# V1_4.net
KiCad netlist of a schematic drawn in Altium Designer
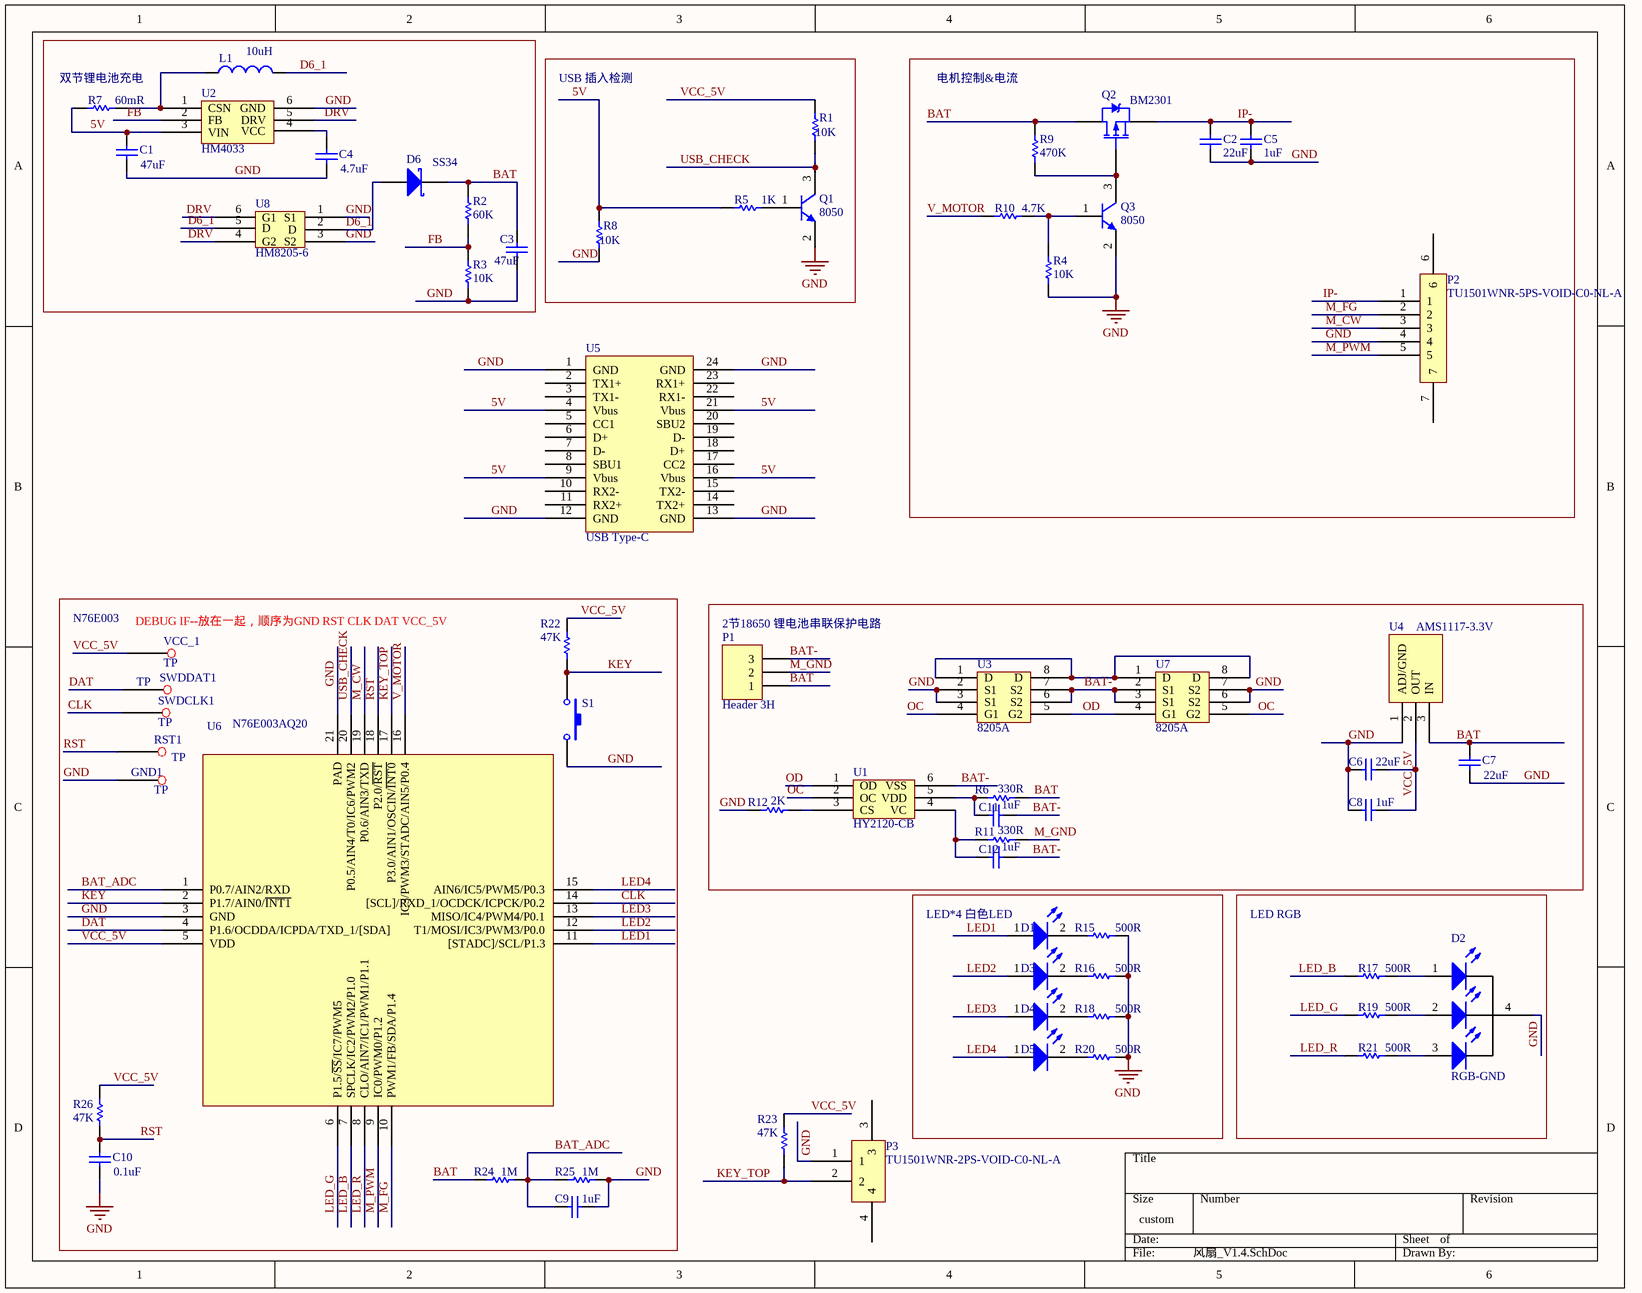
[diagram p0: 风扇_V1.4.SchDoc]

(export (version "E")
  (design (tool "Eeschema 10.0.6"))
  (components
    (comp (ref "C1")
      (value "47uF")
      (footprint "C-0603")
      (description "Capacitor")
      (fields (field (name "PUBLISHER") "Altium Limited"))
      (libsource (lib "Miscellaneous Devices") (part "Cap"))
    )
    (comp (ref "C2")
      (value "22uF")
      (footprint "C-0603")
      (description "Capacitor")
      (fields (field (name "PUBLISHER") "Altium Limited"))
      (libsource (lib "Miscellaneous Devices") (part "Cap"))
    )
    (comp (ref "C3")
      (value "47uF")
      (footprint "C-0603")
      (description "Capacitor")
      (fields (field (name "PUBLISHER") "Altium Limited"))
      (libsource (lib "Miscellaneous Devices") (part "Cap"))
    )
    (comp (ref "C4")
      (value "4.7uF")
      (footprint "C-0402")
      (description "Capacitor")
      (fields (field (name "PUBLISHER") "Altium Limited"))
      (libsource (lib "Miscellaneous Devices") (part "Cap"))
    )
    (comp (ref "C5")
      (value "1uF")
      (footprint "C-0402")
      (description "Capacitor")
      (fields (field (name "PUBLISHER") "Altium Limited"))
      (libsource (lib "Miscellaneous Devices") (part "Cap"))
    )
    (comp (ref "C6")
      (value "22uF")
      (footprint "C-0603")
      (description "Capacitor")
      (fields (field (name "PUBLISHER") "Altium Limited"))
      (libsource (lib "Miscellaneous Devices") (part "Cap"))
    )
    (comp (ref "C7")
      (value "22uF")
      (footprint "C-0603")
      (description "Capacitor")
      (fields (field (name "PUBLISHER") "Altium Limited"))
      (libsource (lib "Miscellaneous Devices") (part "Cap"))
    )
    (comp (ref "C8")
      (value "1uF")
      (footprint "C-0402")
      (description "Capacitor")
      (fields (field (name "PUBLISHER") "Altium Limited"))
      (libsource (lib "Miscellaneous Devices") (part "Cap"))
    )
    (comp (ref "C9")
      (value "1uF")
      (footprint "C-0402")
      (description "Capacitor")
      (fields (field (name "PUBLISHER") "Altium Limited"))
      (libsource (lib "Miscellaneous Devices") (part "Cap"))
    )
    (comp (ref "C10")
      (value "0.1uF")
      (footprint "C-0402")
      (description "Capacitor")
      (fields (field (name "PUBLISHER") "Altium Limited"))
      (libsource (lib "Miscellaneous Devices") (part "Cap"))
    )
    (comp (ref "C11")
      (value "1uF")
      (footprint "C-0402")
      (description "Capacitor")
      (fields (field (name "PUBLISHER") "Altium Limited"))
      (libsource (lib "Miscellaneous Devices") (part "Cap"))
    )
    (comp (ref "C12")
      (value "1uF")
      (footprint "C-0402")
      (description "Capacitor")
      (fields (field (name "PUBLISHER") "Altium Limited"))
      (libsource (lib "Miscellaneous Devices") (part "Cap"))
    )
    (comp (ref "D1")
      (value "LED0")
      (footprint "LED-0603")
      (description "Typical INFRARED GaAs LED")
      (fields (field (name "PUBLISHER") "Altium Limited"))
      (libsource (lib "Miscellaneous Devices") (part "LED0"))
    )
    (comp (ref "D2")
      (value "RGB-GND")
      (footprint "0603*2-LED")
      (libsource (lib "Others_IC_SCH_LIB") (part "RGB-GND"))
    )
    (comp (ref "D3")
      (value "LED0")
      (footprint "LED-0603")
      (description "Typical INFRARED GaAs LED")
      (fields (field (name "PUBLISHER") "Altium Limited"))
      (libsource (lib "Miscellaneous Devices") (part "LED0"))
    )
    (comp (ref "D4")
      (value "LED0")
      (footprint "LED-0603")
      (description "Typical INFRARED GaAs LED")
      (fields (field (name "PUBLISHER") "Altium Limited"))
      (libsource (lib "Miscellaneous Devices") (part "LED0"))
    )
    (comp (ref "D5")
      (value "LED0")
      (footprint "LED-0603")
      (description "Typical INFRARED GaAs LED")
      (fields (field (name "PUBLISHER") "Altium Limited"))
      (libsource (lib "Miscellaneous Devices") (part "LED0"))
    )
    (comp (ref "D6")
      (value "SS34")
      (footprint "HM4033 V1.0:DSMD")
      (description "Schottky Rectifier")
      (fields (field (name "PUBLISHER") "Altium Limited"))
      (libsource (lib "Miscellaneous Devices") (part "Diode 10TQ035"))
    )
    (comp (ref "GND1") (value "TP") (footprint "TP-1.5") (libsource (lib "Others_IC_SCH_LIB") (part "TP")))
    (comp (ref "L1")
      (value "10uH")
      (footprint "L-SMD")
      (description "Inductor")
      (fields (field (name "PUBLISHER") "Altium Limited"))
      (libsource (lib "Miscellaneous Devices") (part "Inductor"))
    )
    (comp (ref "P1")
      (value "Header 3H")
      (footprint "3P-SMT-3*3")
      (description "Header, 3-Pin, Right Angle")
      (fields (field (name "PUBLISHER") "Altium Limited"))
      (libsource (lib "Miscellaneous Connectors") (part "Header 3H"))
    )
    (comp (ref "P2")
      (value "TU1501WNR-5PS-VOID-C0-NL-A")
      (footprint "TU1501WNR-5PS-VOID-*-NL-A")
      (libsource (lib "Others_IC_SCH_LIB") (part "TU1501WNR-5PS-VOID-C0-NL-A"))
    )
    (comp (ref "P3")
      (value "TU1501WNR-2PS-VOID-C0-NL-A")
      (footprint "TU1501WNR-2PS-VOID-*-NL-A")
      (libsource (lib "Others_IC_SCH_LIB") (part "TU1501WNR-2PS-VOID-C0-NL-A"))
    )
    (comp (ref "Q1")
      (value "8050")
      (footprint "SOT-23")
      (description "NPN Bipolar Transistor")
      (fields (field (name "PUBLISHER") "Altium Limited"))
      (libsource (lib "Miscellaneous Devices") (part "NPN"))
    )
    (comp (ref "Q2")
      (value "BM2301")
      (footprint "SOT-23")
      (description "P-Channel Power MOSFET")
      (fields (field (name "PUBLISHER") "Altium Limited"))
      (libsource (lib "Miscellaneous Devices") (part "PMOS-2"))
    )
    (comp (ref "Q3")
      (value "8050")
      (footprint "SOT-23")
      (description "NPN Bipolar Transistor")
      (fields (field (name "PUBLISHER") "Altium Limited"))
      (libsource (lib "Miscellaneous Devices") (part "NPN"))
    )
    (comp (ref "R1")
      (value "10K")
      (footprint "R-0402")
      (description "Resistor")
      (fields (field (name "PUBLISHER") "Altium Limited"))
      (libsource (lib "Miscellaneous Devices") (part "Res1"))
    )
    (comp (ref "R2")
      (value "60K")
      (footprint "R-0402")
      (description "Resistor")
      (fields (field (name "PUBLISHER") "Altium Limited"))
      (libsource (lib "Miscellaneous Devices") (part "Res1"))
    )
    (comp (ref "R3")
      (value "10K")
      (footprint "R-0402")
      (description "Resistor")
      (fields (field (name "PUBLISHER") "Altium Limited"))
      (libsource (lib "Miscellaneous Devices") (part "Res1"))
    )
    (comp (ref "R4")
      (value "10K")
      (footprint "R-0402")
      (description "Resistor")
      (fields (field (name "PUBLISHER") "Altium Limited"))
      (libsource (lib "Miscellaneous Devices") (part "Res1"))
    )
    (comp (ref "R5")
      (value "1K")
      (footprint "R-0402")
      (description "Resistor")
      (fields (field (name "PUBLISHER") "Altium Limited"))
      (libsource (lib "Miscellaneous Devices") (part "Res1"))
    )
    (comp (ref "R6")
      (value "330R")
      (footprint "R-0402")
      (description "Resistor")
      (fields (field (name "PUBLISHER") "Altium Limited"))
      (libsource (lib "Miscellaneous Devices") (part "Res1"))
    )
    (comp (ref "R7")
      (value "60mR")
      (footprint "R-0402")
      (description "Resistor")
      (fields (field (name "PUBLISHER") "Altium Limited"))
      (libsource (lib "Miscellaneous Devices") (part "Res1"))
    )
    (comp (ref "R8")
      (value "10K")
      (footprint "R-0402")
      (description "Resistor")
      (fields (field (name "PUBLISHER") "Altium Limited"))
      (libsource (lib "Miscellaneous Devices") (part "Res1"))
    )
    (comp (ref "R9")
      (value "470K")
      (footprint "R-0402")
      (description "Resistor")
      (fields (field (name "PUBLISHER") "Altium Limited"))
      (libsource (lib "Miscellaneous Devices") (part "Res1"))
    )
    (comp (ref "R10")
      (value "4.7K")
      (footprint "R-0402")
      (description "Resistor")
      (fields (field (name "PUBLISHER") "Altium Limited"))
      (libsource (lib "Miscellaneous Devices") (part "Res1"))
    )
    (comp (ref "R11")
      (value "330R")
      (footprint "R-0402")
      (description "Resistor")
      (fields (field (name "PUBLISHER") "Altium Limited"))
      (libsource (lib "Miscellaneous Devices") (part "Res1"))
    )
    (comp (ref "R12")
      (value "2K")
      (footprint "R-0402")
      (description "Resistor")
      (fields (field (name "PUBLISHER") "Altium Limited"))
      (libsource (lib "Miscellaneous Devices") (part "Res1"))
    )
    (comp (ref "R15")
      (value "500R")
      (footprint "R-0402")
      (description "Resistor")
      (fields (field (name "PUBLISHER") "Altium Limited"))
      (libsource (lib "Miscellaneous Devices") (part "Res1"))
    )
    (comp (ref "R16")
      (value "500R")
      (footprint "R-0402")
      (description "Resistor")
      (fields (field (name "PUBLISHER") "Altium Limited"))
      (libsource (lib "Miscellaneous Devices") (part "Res1"))
    )
    (comp (ref "R17")
      (value "500R")
      (footprint "R-0402")
      (description "Resistor")
      (fields (field (name "PUBLISHER") "Altium Limited"))
      (libsource (lib "Miscellaneous Devices") (part "Res1"))
    )
    (comp (ref "R18")
      (value "500R")
      (footprint "R-0402")
      (description "Resistor")
      (fields (field (name "PUBLISHER") "Altium Limited"))
      (libsource (lib "Miscellaneous Devices") (part "Res1"))
    )
    (comp (ref "R19")
      (value "500R")
      (footprint "R-0402")
      (description "Resistor")
      (fields (field (name "PUBLISHER") "Altium Limited"))
      (libsource (lib "Miscellaneous Devices") (part "Res1"))
    )
    (comp (ref "R20")
      (value "500R")
      (footprint "R-0402")
      (description "Resistor")
      (fields (field (name "PUBLISHER") "Altium Limited"))
      (libsource (lib "Miscellaneous Devices") (part "Res1"))
    )
    (comp (ref "R21")
      (value "500R")
      (footprint "R-0402")
      (description "Resistor")
      (fields (field (name "PUBLISHER") "Altium Limited"))
      (libsource (lib "Miscellaneous Devices") (part "Res1"))
    )
    (comp (ref "R22")
      (value "47K")
      (footprint "R-0402")
      (description "Resistor")
      (fields (field (name "PUBLISHER") "Altium Limited"))
      (libsource (lib "Miscellaneous Devices") (part "Res1"))
    )
    (comp (ref "R23")
      (value "47K")
      (footprint "R-0402")
      (description "Resistor")
      (fields (field (name "PUBLISHER") "Altium Limited"))
      (libsource (lib "Miscellaneous Devices") (part "Res1"))
    )
    (comp (ref "R24")
      (value "1M")
      (footprint "R-0402")
      (description "Resistor")
      (fields (field (name "PUBLISHER") "Altium Limited"))
      (libsource (lib "Miscellaneous Devices") (part "Res1"))
    )
    (comp (ref "R25")
      (value "1M")
      (footprint "R-0402")
      (description "Resistor")
      (fields (field (name "PUBLISHER") "Altium Limited"))
      (libsource (lib "Miscellaneous Devices") (part "Res1"))
    )
    (comp (ref "R26")
      (value "47K")
      (footprint "R-0402")
      (description "Resistor")
      (fields (field (name "PUBLISHER") "Altium Limited"))
      (libsource (lib "Miscellaneous Devices") (part "Res1"))
    )
    (comp (ref "RST1") (value "TP") (footprint "TP-1.5") (libsource (lib "Others_IC_SCH_LIB") (part "TP")))
    (comp (ref "S1")
      (value "SW-PB")
      (footprint "SWITCH-4P-SMT")
      (description "Switch")
      (fields (field (name "PUBLISHER") "Altium Limited"))
      (libsource (lib "Miscellaneous Devices") (part "SW-PB"))
    )
    (comp (ref "SWDCLK1") (value "TP") (footprint "TP-1.5") (libsource (lib "Others_IC_SCH_LIB") (part "TP")))
    (comp (ref "SWDDAT1") (value "TP") (footprint "TP-1.5") (libsource (lib "Others_IC_SCH_LIB") (part "TP")))
    (comp (ref "U1")
      (value "HY2120-CB")
      (footprint "SOT-23-6L")
      (libsource (lib "Others_IC_SCH_LIB") (part "HY2120"))
    )
    (comp (ref "U2")
      (value "HM4033")
      (footprint "SOT-23-6L")
      (libsource (lib "Others_IC_SCH_LIB") (part "HM4033"))
    )
    (comp (ref "U3")
      (value "8205A")
      (footprint "TSSOP8")
      (libsource (lib "Others_IC_SCH_LIB") (part "8205A"))
    )
    (comp (ref "U4")
      (value "AMS1117-3.3V")
      (footprint "SOT-223")
      (libsource (lib "Others_IC_SCH_LIB") (part "AMS1117"))
    )
    (comp (ref "U5")
      (value "USB Type-C")
      (footprint "USB-type C")
      (libsource (lib "Others_IC_SCH_LIB") (part "USB Type-C"))
    )
    (comp (ref "U6")
      (value "N76E003AQ20")
      (footprint "QFN-20 0.4mm")
      (libsource (lib "Others_IC_SCH_LIB") (part "N76E003AQ20"))
    )
    (comp (ref "U7")
      (value "8205A")
      (footprint "TSSOP8")
      (libsource (lib "Others_IC_SCH_LIB") (part "8205A"))
    )
    (comp (ref "U8")
      (value "HM8205-6")
      (footprint "SOT-23-6L")
      (libsource (lib "Others_IC_SCH_LIB") (part "HM8205-6"))
    )
    (comp (ref "VCC_1") (value "TP") (footprint "TP-1.5") (libsource (lib "Others_IC_SCH_LIB") (part "TP")))
  )
  (nets
    (net (code "1") (name "/5V") (class "Default")
      (node (ref "C1") (pin "1") (pinfunction "1_1") (pintype "passive"))
      (node (ref "R5") (pin "1") (pinfunction "1_1") (pintype "passive"))
      (node (ref "R7") (pin "2") (pinfunction "2_2") (pintype "passive"))
      (node (ref "R8") (pin "1") (pinfunction "1_1") (pintype "passive"))
      (node (ref "U2") (pin "3") (pinfunction "VIN_3") (pintype "passive"))
      (node (ref "U5") (pin "16") (pinfunction "Vbus_16") (pintype "passive"))
      (node (ref "U5") (pin "21") (pinfunction "Vbus_21") (pintype "passive"))
      (node (ref "U5") (pin "4") (pinfunction "Vbus_4") (pintype "passive"))
      (node (ref "U5") (pin "9") (pinfunction "Vbus_9") (pintype "passive"))
    )
    (net (code "2") (name "/BAT") (class "Default")
      (node (ref "C3") (pin "2") (pinfunction "2_2") (pintype "passive"))
      (node (ref "C7") (pin "2") (pinfunction "2_2") (pintype "passive"))
      (node (ref "D6") (pin "1") (pinfunction "K_1") (pintype "passive"))
      (node (ref "P1") (pin "1") (pinfunction "1_1") (pintype "passive"))
      (node (ref "Q2") (pin "2") (pinfunction "D_2") (pintype "passive"))
      (node (ref "R2") (pin "1") (pinfunction "1_1") (pintype "passive"))
      (node (ref "R24") (pin "1") (pinfunction "1_1") (pintype "passive"))
      (node (ref "R6") (pin "2") (pinfunction "2_2") (pintype "passive"))
      (node (ref "R9") (pin "2") (pinfunction "2_2") (pintype "passive"))
      (node (ref "U4") (pin "3") (pinfunction "IN_3") (pintype "passive"))
    )
    (net (code "3") (name "/BAT-") (class "Default")
      (node (ref "C11") (pin "1") (pinfunction "1_1") (pintype "passive"))
      (node (ref "C12") (pin "1") (pinfunction "1_1") (pintype "passive"))
      (node (ref "P1") (pin "3") (pinfunction "3_3") (pintype "passive"))
      (node (ref "U1") (pin "6") (pinfunction "VSS_6") (pintype "passive"))
      (node (ref "U3") (pin "6") (pinfunction "S2_6") (pintype "passive"))
      (node (ref "U3") (pin "7") (pinfunction "S2_7") (pintype "passive"))
      (node (ref "U7") (pin "2") (pinfunction "S1_2") (pintype "passive"))
      (node (ref "U7") (pin "3") (pinfunction "S1_3") (pintype "passive"))
    )
    (net (code "4") (name "/BAT_ADC") (class "Default")
      (node (ref "C9") (pin "2") (pinfunction "2_2") (pintype "passive"))
      (node (ref "R24") (pin "2") (pinfunction "2_2") (pintype "passive"))
      (node (ref "R25") (pin "1") (pinfunction "1_1") (pintype "passive"))
      (node (ref "U6") (pin "1") (pinfunction "P0.7/AIN2/RXD_1") (pintype "passive"))
    )
    (net (code "5") (name "/CLK") (class "Default")
      (node (ref "SWDCLK1") (pin "1") (pinfunction "1_1") (pintype "passive"))
      (node (ref "U6") (pin "14") (pinfunction "[SCL]/RXD_1/OCDCK/ICPCK/P0.2_14") (pintype "passive"))
    )
    (net (code "6") (name "/D6_1") (class "Default")
      (node (ref "D6") (pin "3") (pinfunction "A_3") (pintype "passive"))
      (node (ref "L1") (pin "2") (pinfunction "2_2") (pintype "passive"))
      (node (ref "U8") (pin "2") (pinfunction "D_2") (pintype "passive"))
      (node (ref "U8") (pin "5") (pinfunction "D_5") (pintype "passive"))
    )
    (net (code "7") (name "/DAT") (class "Default")
      (node (ref "SWDDAT1") (pin "1") (pinfunction "1_1") (pintype "passive"))
      (node (ref "U6") (pin "4") (pinfunction "P1.6/OCDDA/ICPDA/TXD_1/[SDA]_4") (pintype "passive"))
    )
    (net (code "8") (name "/DRV") (class "Default")
      (node (ref "U2") (pin "5") (pinfunction "DRV_5") (pintype "passive"))
      (node (ref "U8") (pin "4") (pinfunction "G2_4") (pintype "passive"))
      (node (ref "U8") (pin "6") (pinfunction "G1_6") (pintype "passive"))
    )
    (net (code "9") (name "/FB") (class "Default")
      (node (ref "R2") (pin "2") (pinfunction "2_2") (pintype "passive"))
      (node (ref "R3") (pin "1") (pinfunction "1_1") (pintype "passive"))
      (node (ref "U2") (pin "2") (pinfunction "FB_2") (pintype "passive"))
    )
    (net (code "10") (name "/IP-") (class "Default")
      (node (ref "C2") (pin "2") (pinfunction "2_2") (pintype "passive"))
      (node (ref "C5") (pin "2") (pinfunction "2_2") (pintype "passive"))
      (node (ref "P2") (pin "1") (pinfunction "1_1") (pintype "passive"))
      (node (ref "Q2") (pin "3") (pinfunction "S_3") (pintype "passive"))
    )
    (net (code "11") (name "/KEY") (class "Default")
      (node (ref "R22") (pin "1") (pinfunction "1_1") (pintype "passive"))
      (node (ref "S1") (pin "1") (pinfunction "1_1") (pintype "passive"))
      (node (ref "U6") (pin "2") (pinfunction "P1.7/AIN0/~{INT1}_2") (pintype "passive"))
    )
    (net (code "12") (name "/KEY_TOP") (class "Default")
      (node (ref "P3") (pin "2") (pinfunction "2_2") (pintype "passive"))
      (node (ref "R23") (pin "1") (pinfunction "1_1") (pintype "passive"))
      (node (ref "U6") (pin "17") (pinfunction "P3.0/AIN1/OSCIN/~{INT0}_17") (pintype "passive"))
    )
    (net (code "13") (name "/LED1") (class "Default")
      (node (ref "D1") (pin "1") (pinfunction "A_1") (pintype "passive"))
      (node (ref "U6") (pin "11") (pinfunction "[STADC]/SCL/P1.3_11") (pintype "passive"))
    )
    (net (code "14") (name "/LED2") (class "Default")
      (node (ref "D3") (pin "1") (pinfunction "A_1") (pintype "passive"))
      (node (ref "U6") (pin "12") (pinfunction "T1/MOSI/IC3/PWM3/P0.0_12") (pintype "passive"))
    )
    (net (code "15") (name "/LED3") (class "Default")
      (node (ref "D4") (pin "1") (pinfunction "A_1") (pintype "passive"))
      (node (ref "U6") (pin "13") (pinfunction "MISO/IC4/PWM4/P0.1_13") (pintype "passive"))
    )
    (net (code "16") (name "/LED4") (class "Default")
      (node (ref "D5") (pin "1") (pinfunction "A_1") (pintype "passive"))
      (node (ref "U6") (pin "15") (pinfunction "AIN6/IC5/PWM5/P0.3_15") (pintype "passive"))
    )
    (net (code "17") (name "/LED_B") (class "Default")
      (node (ref "R17") (pin "1") (pinfunction "1_1") (pintype "passive"))
      (node (ref "U6") (pin "7") (pinfunction "SPCLK/IC2/PWM2/P1.0_7") (pintype "passive"))
    )
    (net (code "18") (name "/LED_G") (class "Default")
      (node (ref "R19") (pin "1") (pinfunction "1_1") (pintype "passive"))
      (node (ref "U6") (pin "6") (pinfunction "P1.5/~{SS}/IC7/PWM5_6") (pintype "passive"))
    )
    (net (code "19") (name "/LED_R") (class "Default")
      (node (ref "R21") (pin "1") (pinfunction "1_1") (pintype "passive"))
      (node (ref "U6") (pin "8") (pinfunction "CLO/AIN7/IC1/PWM1/P1.1_8") (pintype "passive"))
    )
    (net (code "20") (name "/M_CW") (class "Default")
      (node (ref "P2") (pin "3") (pinfunction "3_3") (pintype "passive"))
      (node (ref "U6") (pin "19") (pinfunction "P0.6/AIN3/TXD_19") (pintype "passive"))
    )
    (net (code "21") (name "/M_FG") (class "Default")
      (node (ref "P2") (pin "2") (pinfunction "2_2") (pintype "passive"))
      (node (ref "U6") (pin "10") (pinfunction "PWM1/FB/SDA/P1.4_10") (pintype "passive"))
    )
    (net (code "22") (name "/M_GND") (class "Default")
      (node (ref "P1") (pin "2") (pinfunction "2_2") (pintype "passive"))
      (node (ref "R11") (pin "2") (pinfunction "2_2") (pintype "passive"))
    )
    (net (code "23") (name "/M_PWM") (class "Default")
      (node (ref "P2") (pin "5") (pinfunction "5_5") (pintype "passive"))
      (node (ref "U6") (pin "9") (pinfunction "IC0/PWM0/P1.2_9") (pintype "passive"))
    )
    (net (code "24") (name "/OC") (class "Default")
      (node (ref "U1") (pin "2") (pinfunction "OC_2") (pintype "passive"))
      (node (ref "U3") (pin "4") (pinfunction "G1_4") (pintype "passive"))
      (node (ref "U7") (pin "5") (pinfunction "G2_5") (pintype "passive"))
    )
    (net (code "25") (name "/OD") (class "Default")
      (node (ref "U1") (pin "1") (pinfunction "OD_1") (pintype "passive"))
      (node (ref "U3") (pin "5") (pinfunction "G2_5") (pintype "passive"))
      (node (ref "U7") (pin "4") (pinfunction "G1_4") (pintype "passive"))
    )
    (net (code "26") (name "/RST") (class "Default")
      (node (ref "C10") (pin "2") (pinfunction "2_2") (pintype "passive"))
      (node (ref "R26") (pin "1") (pinfunction "1_1") (pintype "passive"))
      (node (ref "RST1") (pin "1") (pinfunction "1_1") (pintype "passive"))
      (node (ref "U6") (pin "18") (pinfunction "P2.0/~{RST}_18") (pintype "passive"))
    )
    (net (code "27") (name "/USB_CHECK") (class "Default")
      (node (ref "Q1") (pin "3") (pinfunction "C_3") (pintype "passive"))
      (node (ref "R1") (pin "1") (pinfunction "1_1") (pintype "passive"))
      (node (ref "U6") (pin "20") (pinfunction "P0.5/AIN4/T0/IC6/PWM2_20") (pintype "passive"))
    )
    (net (code "28") (name "/VCC_5V") (class "Default")
      (node (ref "C6") (pin "2") (pinfunction "2_2") (pintype "passive"))
      (node (ref "C8") (pin "2") (pinfunction "2_2") (pintype "passive"))
      (node (ref "R1") (pin "2") (pinfunction "2_2") (pintype "passive"))
      (node (ref "R22") (pin "2") (pinfunction "2_2") (pintype "passive"))
      (node (ref "R23") (pin "2") (pinfunction "2_2") (pintype "passive"))
      (node (ref "R26") (pin "2") (pinfunction "2_2") (pintype "passive"))
      (node (ref "U4") (pin "2") (pinfunction "OUT_2") (pintype "passive"))
      (node (ref "U6") (pin "5") (pinfunction "VDD_5") (pintype "passive"))
      (node (ref "VCC_1") (pin "1") (pinfunction "1_1") (pintype "passive"))
    )
    (net (code "29") (name "/V_MOTOR") (class "Default")
      (node (ref "R10") (pin "1") (pinfunction "1_1") (pintype "passive"))
      (node (ref "U6") (pin "16") (pinfunction "IC3/PWM3/STADC/AIN5/P0.4_16") (pintype "passive"))
    )
    (net (code "30") (name "GND") (class "Default")
      (node (ref "C1") (pin "2") (pinfunction "2_2") (pintype "passive"))
      (node (ref "C10") (pin "1") (pinfunction "1_1") (pintype "passive"))
      (node (ref "C2") (pin "1") (pinfunction "1_1") (pintype "passive"))
      (node (ref "C3") (pin "1") (pinfunction "1_1") (pintype "passive"))
      (node (ref "C4") (pin "2") (pinfunction "2_2") (pintype "passive"))
      (node (ref "C5") (pin "1") (pinfunction "1_1") (pintype "passive"))
      (node (ref "C6") (pin "1") (pinfunction "1_1") (pintype "passive"))
      (node (ref "C7") (pin "1") (pinfunction "1_1") (pintype "passive"))
      (node (ref "C8") (pin "1") (pinfunction "1_1") (pintype "passive"))
      (node (ref "C9") (pin "1") (pinfunction "1_1") (pintype "passive"))
      (node (ref "D2") (pin "4") (pinfunction "4_4") (pintype "passive"))
      (node (ref "GND1") (pin "1") (pinfunction "1_1") (pintype "passive"))
      (node (ref "P2") (pin "4") (pinfunction "4_4") (pintype "passive"))
      (node (ref "P3") (pin "1") (pinfunction "1_1") (pintype "passive"))
      (node (ref "Q1") (pin "2") (pinfunction "E_2") (pintype "passive"))
      (node (ref "Q3") (pin "2") (pinfunction "E_2") (pintype "passive"))
      (node (ref "R12") (pin "1") (pinfunction "1_1") (pintype "passive"))
      (node (ref "R15") (pin "2") (pinfunction "2_2") (pintype "passive"))
      (node (ref "R16") (pin "2") (pinfunction "2_2") (pintype "passive"))
      (node (ref "R18") (pin "2") (pinfunction "2_2") (pintype "passive"))
      (node (ref "R20") (pin "2") (pinfunction "2_2") (pintype "passive"))
      (node (ref "R25") (pin "2") (pinfunction "2_2") (pintype "passive"))
      (node (ref "R3") (pin "2") (pinfunction "2_2") (pintype "passive"))
      (node (ref "R4") (pin "1") (pinfunction "1_1") (pintype "passive"))
      (node (ref "R8") (pin "2") (pinfunction "2_2") (pintype "passive"))
      (node (ref "S1") (pin "2") (pinfunction "2_2") (pintype "passive"))
      (node (ref "U2") (pin "6") (pinfunction "GND_6") (pintype "passive"))
      (node (ref "U3") (pin "2") (pinfunction "S1_2") (pintype "passive"))
      (node (ref "U3") (pin "3") (pinfunction "S1_3") (pintype "passive"))
      (node (ref "U4") (pin "1") (pinfunction "ADJ/GND_1") (pintype "passive"))
      (node (ref "U5") (pin "1") (pinfunction "GND_1") (pintype "passive"))
      (node (ref "U5") (pin "12") (pinfunction "GND_12") (pintype "passive"))
      (node (ref "U5") (pin "13") (pinfunction "GND_13") (pintype "passive"))
      (node (ref "U5") (pin "24") (pinfunction "GND_24") (pintype "passive"))
      (node (ref "U6") (pin "21") (pinfunction "PAD_21") (pintype "passive"))
      (node (ref "U6") (pin "3") (pinfunction "GND_3") (pintype "passive"))
      (node (ref "U7") (pin "6") (pinfunction "S2_6") (pintype "passive"))
      (node (ref "U7") (pin "7") (pinfunction "S2_7") (pintype "passive"))
      (node (ref "U8") (pin "1") (pinfunction "S1_1") (pintype "passive"))
      (node (ref "U8") (pin "3") (pinfunction "S2_3") (pintype "passive"))
    )
    (net (code "31") (name "Net-(D1-K)") (class "Default")
      (node (ref "D1") (pin "2") (pinfunction "K_2") (pintype "passive"))
      (node (ref "R15") (pin "1") (pinfunction "1_1") (pintype "passive"))
    )
    (net (code "32") (name "Net-(D2-Pad1)") (class "Default")
      (node (ref "D2") (pin "1") (pinfunction "1_1") (pintype "passive"))
      (node (ref "R17") (pin "2") (pinfunction "2_2") (pintype "passive"))
    )
    (net (code "33") (name "Net-(D2-Pad2)") (class "Default")
      (node (ref "D2") (pin "2") (pinfunction "2_2") (pintype "passive"))
      (node (ref "R19") (pin "2") (pinfunction "2_2") (pintype "passive"))
    )
    (net (code "34") (name "Net-(D2-Pad3)") (class "Default")
      (node (ref "D2") (pin "3") (pinfunction "3_3") (pintype "passive"))
      (node (ref "R21") (pin "2") (pinfunction "2_2") (pintype "passive"))
    )
    (net (code "35") (name "Net-(D3-K)") (class "Default")
      (node (ref "D3") (pin "2") (pinfunction "K_2") (pintype "passive"))
      (node (ref "R16") (pin "1") (pinfunction "1_1") (pintype "passive"))
    )
    (net (code "36") (name "Net-(D4-K)") (class "Default")
      (node (ref "D4") (pin "2") (pinfunction "K_2") (pintype "passive"))
      (node (ref "R18") (pin "1") (pinfunction "1_1") (pintype "passive"))
    )
    (net (code "37") (name "Net-(D5-K)") (class "Default")
      (node (ref "D5") (pin "2") (pinfunction "K_2") (pintype "passive"))
      (node (ref "R20") (pin "1") (pinfunction "1_1") (pintype "passive"))
    )
    (net (code "38") (name "Net-(Q1-B)") (class "Default")
      (node (ref "Q1") (pin "1") (pinfunction "B_1") (pintype "passive"))
      (node (ref "R5") (pin "2") (pinfunction "2_2") (pintype "passive"))
    )
    (net (code "39") (name "Net-(Q2-G)") (class "Default")
      (node (ref "Q2") (pin "1") (pinfunction "G_1") (pintype "passive"))
      (node (ref "Q3") (pin "3") (pinfunction "C_3") (pintype "passive"))
      (node (ref "R9") (pin "1") (pinfunction "1_1") (pintype "passive"))
    )
    (net (code "40") (name "Net-(Q3-B)") (class "Default")
      (node (ref "Q3") (pin "1") (pinfunction "B_1") (pintype "passive"))
      (node (ref "R10") (pin "2") (pinfunction "2_2") (pintype "passive"))
      (node (ref "R4") (pin "2") (pinfunction "2_2") (pintype "passive"))
    )
    (net (code "41") (name "Net-(U1-CS)") (class "Default")
      (node (ref "R12") (pin "2") (pinfunction "2_2") (pintype "passive"))
      (node (ref "U1") (pin "3") (pinfunction "CS_3") (pintype "passive"))
    )
    (net (code "42") (name "Net-(U1-VC)") (class "Default")
      (node (ref "C12") (pin "2") (pinfunction "2_2") (pintype "passive"))
      (node (ref "R11") (pin "1") (pinfunction "1_1") (pintype "passive"))
      (node (ref "U1") (pin "4") (pinfunction "VC_4") (pintype "passive"))
    )
    (net (code "43") (name "Net-(U1-VDD)") (class "Default")
      (node (ref "C11") (pin "2") (pinfunction "2_2") (pintype "passive"))
      (node (ref "R6") (pin "1") (pinfunction "1_1") (pintype "passive"))
      (node (ref "U1") (pin "5") (pinfunction "VDD_5") (pintype "passive"))
    )
    (net (code "44") (name "Net-(U2-CSN)") (class "Default")
      (node (ref "L1") (pin "1") (pinfunction "1_1") (pintype "passive"))
      (node (ref "R7") (pin "1") (pinfunction "1_1") (pintype "passive"))
      (node (ref "U2") (pin "1") (pinfunction "CSN_1") (pintype "passive"))
    )
    (net (code "45") (name "Net-(U2-VCC)") (class "Default")
      (node (ref "C4") (pin "1") (pinfunction "1_1") (pintype "passive"))
      (node (ref "U2") (pin "4") (pinfunction "VCC_4") (pintype "passive"))
    )
    (net (code "46") (name "Net-(U3-D-Pad1)") (class "Default")
      (node (ref "U3") (pin "1") (pinfunction "D_1") (pintype "passive"))
      (node (ref "U3") (pin "8") (pinfunction "D_8") (pintype "passive"))
      (node (ref "U7") (pin "1") (pinfunction "D_1") (pintype "passive"))
      (node (ref "U7") (pin "8") (pinfunction "D_8") (pintype "passive"))
    )
    (net (code "47") (name "unconnected-(P2-Pad6)") (class "Default")
      (node (ref "P2") (pin "6") (pinfunction "6_6") (pintype "passive"))
    )
    (net (code "48") (name "unconnected-(P2-Pad7)") (class "Default")
      (node (ref "P2") (pin "7") (pinfunction "7_7") (pintype "passive"))
    )
    (net (code "49") (name "unconnected-(P3-Pad3)") (class "Default")
      (node (ref "P3") (pin "3") (pinfunction "3_3") (pintype "passive"))
    )
    (net (code "50") (name "unconnected-(P3-Pad4)") (class "Default")
      (node (ref "P3") (pin "4") (pinfunction "4_4") (pintype "passive"))
    )
    (net (code "51") (name "unconnected-(U5-CC1-Pad5)") (class "Default")
      (node (ref "U5") (pin "5") (pinfunction "CC1_5") (pintype "passive"))
    )
    (net (code "52") (name "unconnected-(U5-CC2-Pad17)") (class "Default")
      (node (ref "U5") (pin "17") (pinfunction "CC2_17") (pintype "passive"))
    )
    (net (code "53") (name "unconnected-(U5-D+-Pad6)") (class "Default")
      (node (ref "U5") (pin "6") (pinfunction "D+_6") (pintype "passive"))
    )
    (net (code "54") (name "unconnected-(U5-D+-Pad18)") (class "Default")
      (node (ref "U5") (pin "18") (pinfunction "D+_18") (pintype "passive"))
    )
    (net (code "55") (name "unconnected-(U5-D--Pad7)") (class "Default")
      (node (ref "U5") (pin "7") (pinfunction "D-_7") (pintype "passive"))
    )
    (net (code "56") (name "unconnected-(U5-D--Pad19)") (class "Default")
      (node (ref "U5") (pin "19") (pinfunction "D-_19") (pintype "passive"))
    )
    (net (code "57") (name "unconnected-(U5-RX1+-Pad23)") (class "Default")
      (node (ref "U5") (pin "23") (pinfunction "RX1+_23") (pintype "passive"))
    )
    (net (code "58") (name "unconnected-(U5-RX1--Pad22)") (class "Default")
      (node (ref "U5") (pin "22") (pinfunction "RX1-_22") (pintype "passive"))
    )
    (net (code "59") (name "unconnected-(U5-RX2+-Pad11)") (class "Default")
      (node (ref "U5") (pin "11") (pinfunction "RX2+_11") (pintype "passive"))
    )
    (net (code "60") (name "unconnected-(U5-RX2--Pad10)") (class "Default")
      (node (ref "U5") (pin "10") (pinfunction "RX2-_10") (pintype "passive"))
    )
    (net (code "61") (name "unconnected-(U5-SBU1-Pad8)") (class "Default")
      (node (ref "U5") (pin "8") (pinfunction "SBU1_8") (pintype "passive"))
    )
    (net (code "62") (name "unconnected-(U5-SBU2-Pad20)") (class "Default")
      (node (ref "U5") (pin "20") (pinfunction "SBU2_20") (pintype "passive"))
    )
    (net (code "63") (name "unconnected-(U5-TX1+-Pad2)") (class "Default")
      (node (ref "U5") (pin "2") (pinfunction "TX1+_2") (pintype "passive"))
    )
    (net (code "64") (name "unconnected-(U5-TX1--Pad3)") (class "Default")
      (node (ref "U5") (pin "3") (pinfunction "TX1-_3") (pintype "passive"))
    )
    (net (code "65") (name "unconnected-(U5-TX2+-Pad14)") (class "Default")
      (node (ref "U5") (pin "14") (pinfunction "TX2+_14") (pintype "passive"))
    )
    (net (code "66") (name "unconnected-(U5-TX2--Pad15)") (class "Default")
      (node (ref "U5") (pin "15") (pinfunction "TX2-_15") (pintype "passive"))
    )
  )
)
